# IO.net
KiCad netlist of a schematic drawn in Altium Designer
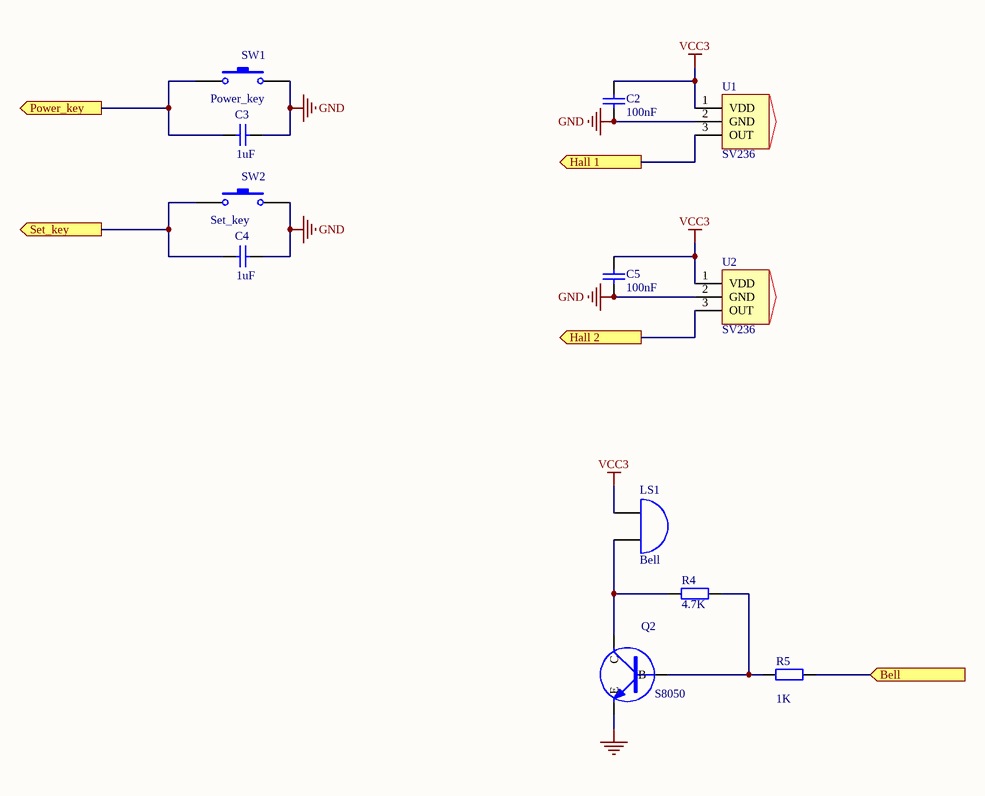
[diagram p0: IO.SchDoc]

(export (version "E")
  (design (tool "Eeschema 10.0.6"))
  (components
    (comp (ref "C2")
      (value "100nF")
      (footprint "RAD-0.3")
      (description "Capacitor")
      (fields (field (name "Comment") "Cap") (field (name "PUBLISHER") "Altium Limited"))
      (libsource (lib "Miscellaneous Devices") (part "Cap"))
    )
    (comp (ref "C3")
      (value "1uF")
      (description "Capacitor")
      (fields (field (name "Comment") "Cap") (field (name "PUBLISHER") "Altium Limited"))
      (libsource (lib "Miscellaneous Devices") (part "Cap"))
    )
    (comp (ref "C4")
      (value "1uF")
      (description "Capacitor")
      (fields (field (name "Comment") "Cap") (field (name "PUBLISHER") "Altium Limited"))
      (libsource (lib "Miscellaneous Devices") (part "Cap"))
    )
    (comp (ref "C5")
      (value "100nF")
      (footprint "RAD-0.3")
      (description "Capacitor")
      (fields (field (name "Comment") "Cap") (field (name "PUBLISHER") "Altium Limited"))
      (libsource (lib "Miscellaneous Devices") (part "Cap"))
    )
    (comp (ref "LS1")
      (value "Bell")
      (description "Electrical Bell")
      (fields (field (name "PUBLISHER") "Altium Limited"))
      (libsource (lib "Miscellaneous Devices") (part "Bell"))
    )
    (comp (ref "Q2")
      (value "S8050")
      (footprint "SOT-23")
      (description "NPN Transistor")
      (libsource (lib "*") (part "NPN"))
    )
    (comp (ref "R4")
      (value "4.7K")
      (description "Resistor")
      (fields (field (name "Comment") "100K") (field (name "PUBLISHER") "Altium Limited"))
      (libsource (lib "Miscellaneous Devices") (part "Res2"))
    )
    (comp (ref "R5")
      (value "1K")
      (description "Resistor")
      (fields (field (name "Comment") "Res2") (field (name "PUBLISHER") "Altium Limited"))
      (libsource (lib "") (part "Res2_1"))
    )
    (comp (ref "SW1")
      (value "Power_key")
      (description "Switch")
      (fields (field (name "PUBLISHER") "Altium Limited"))
      (libsource (lib "Miscellaneous Devices") (part "SW-PB"))
    )
    (comp (ref "SW2")
      (value "Set_key")
      (description "Switch")
      (fields (field (name "PUBLISHER") "Altium Limited"))
      (libsource (lib "Miscellaneous Devices") (part "SW-PB"))
    )
    (comp (ref "U1") (value "SV236") (footprint "sot-23-3") (libsource (lib "*") (part "霍尔44E 938")))
    (comp (ref "U2") (value "SV236") (footprint "sot-23-3") (libsource (lib "*") (part "霍尔44E 938")))
  )
  (nets
    (net (code "1") (name "/Bell") (class "Default")
      (node (ref "R5") (pin "2") (pinfunction "2_2") (pintype "passive"))
    )
    (net (code "2") (name "/Hall 1") (class "Default")
      (node (ref "U1") (pin "3") (pinfunction "OUT_3") (pintype "passive"))
    )
    (net (code "3") (name "/Hall 2") (class "Default")
      (node (ref "U2") (pin "3") (pinfunction "OUT_3") (pintype "passive"))
    )
    (net (code "4") (name "/Power_key") (class "Default")
      (node (ref "C3") (pin "2") (pinfunction "2_2") (pintype "passive"))
      (node (ref "SW1") (pin "1") (pinfunction "1_1") (pintype "passive"))
    )
    (net (code "5") (name "/Set_key") (class "Default")
      (node (ref "C4") (pin "2") (pinfunction "2_2") (pintype "passive"))
      (node (ref "SW2") (pin "1") (pinfunction "1_1") (pintype "passive"))
    )
    (net (code "6") (name "GND") (class "Default")
      (node (ref "C2") (pin "2") (pinfunction "2_2") (pintype "passive"))
      (node (ref "C3") (pin "1") (pinfunction "1_1") (pintype "passive"))
      (node (ref "C4") (pin "1") (pinfunction "1_1") (pintype "passive"))
      (node (ref "C5") (pin "2") (pinfunction "2_2") (pintype "passive"))
      (node (ref "Q2") (pin "2") (pinfunction "E_2") (pintype "passive"))
      (node (ref "SW1") (pin "2") (pinfunction "2_2") (pintype "passive"))
      (node (ref "SW2") (pin "2") (pinfunction "2_2") (pintype "passive"))
      (node (ref "U1") (pin "2") (pinfunction "GND_2") (pintype "passive"))
      (node (ref "U2") (pin "2") (pinfunction "GND_2") (pintype "passive"))
    )
    (net (code "7") (name "Net-(LS1-B)") (class "Default")
      (node (ref "LS1") (pin "2") (pinfunction "B_2") (pintype "passive"))
      (node (ref "Q2") (pin "3") (pinfunction "C_3") (pintype "passive"))
      (node (ref "R4") (pin "2") (pinfunction "2_2") (pintype "passive"))
    )
    (net (code "8") (name "Net-(Q2-B)") (class "Default")
      (node (ref "Q2") (pin "1") (pinfunction "B_1") (pintype "passive"))
      (node (ref "R4") (pin "1") (pinfunction "1_1") (pintype "passive"))
      (node (ref "R5") (pin "1") (pinfunction "1_1") (pintype "passive"))
    )
    (net (code "9") (name "VCC3") (class "Default")
      (node (ref "C2") (pin "1") (pinfunction "1_1") (pintype "passive"))
      (node (ref "C5") (pin "1") (pinfunction "1_1") (pintype "passive"))
      (node (ref "LS1") (pin "1") (pinfunction "A_1") (pintype "passive"))
      (node (ref "U1") (pin "1") (pinfunction "VDD_1") (pintype "passive"))
      (node (ref "U2") (pin "1") (pinfunction "VDD_1") (pintype "passive"))
    )
  )
)
